# sonar_peripherals.net
KiCad netlist of a schematic drawn in Altium Designer
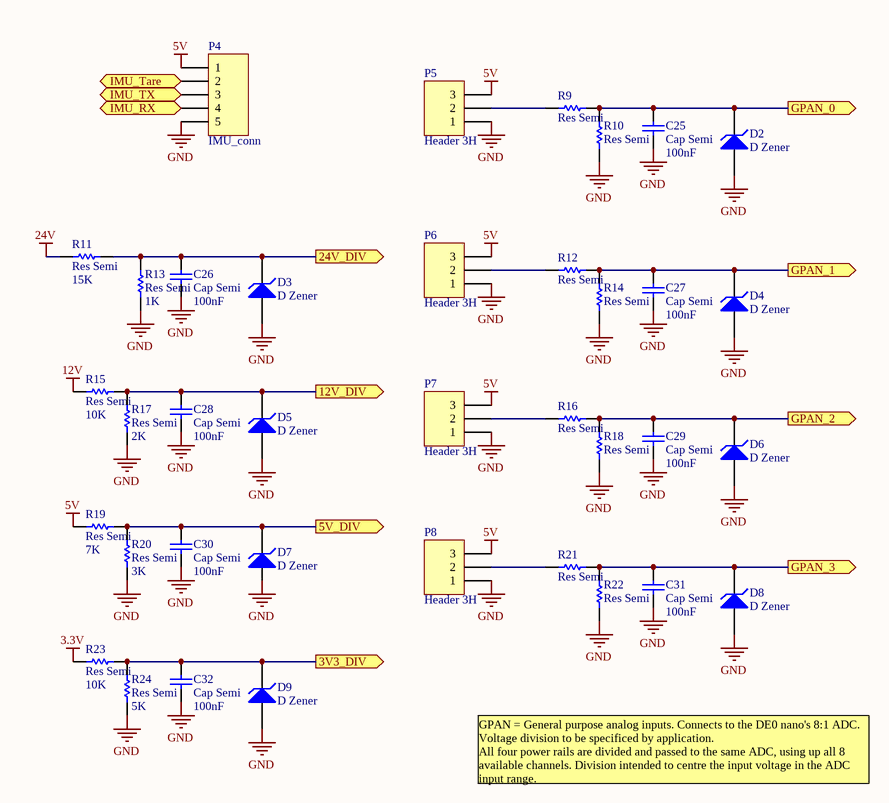
[diagram p0: sonar_peripherals.SchDoc]

(export (version "E")
  (design (tool "Eeschema 10.0.6"))
  (components
    (comp (ref "C25")
      (value "Cap Semi")
      (footprint "C0805")
      (description "Capacitor (Semiconductor SIM Model)")
      (fields (field (name "ALTIUM_VALUE") "100nF") (field (name "PUBLISHER") "Altium Limited"))
      (libsource (lib "Miscellaneous Devices") (part "Cap Semi"))
    )
    (comp (ref "C26")
      (value "Cap Semi")
      (footprint "C0805")
      (description "Capacitor (Semiconductor SIM Model)")
      (fields (field (name "ALTIUM_VALUE") "100nF") (field (name "PUBLISHER") "Altium Limited"))
      (libsource (lib "Miscellaneous Devices") (part "Cap Semi"))
    )
    (comp (ref "C27")
      (value "Cap Semi")
      (footprint "C0805")
      (description "Capacitor (Semiconductor SIM Model)")
      (fields (field (name "ALTIUM_VALUE") "100nF") (field (name "PUBLISHER") "Altium Limited"))
      (libsource (lib "Miscellaneous Devices") (part "Cap Semi"))
    )
    (comp (ref "C28")
      (value "Cap Semi")
      (footprint "C0805")
      (description "Capacitor (Semiconductor SIM Model)")
      (fields (field (name "ALTIUM_VALUE") "100nF") (field (name "PUBLISHER") "Altium Limited"))
      (libsource (lib "Miscellaneous Devices") (part "Cap Semi"))
    )
    (comp (ref "C29")
      (value "Cap Semi")
      (footprint "C0805")
      (description "Capacitor (Semiconductor SIM Model)")
      (fields (field (name "ALTIUM_VALUE") "100nF") (field (name "PUBLISHER") "Altium Limited"))
      (libsource (lib "Miscellaneous Devices") (part "Cap Semi"))
    )
    (comp (ref "C30")
      (value "Cap Semi")
      (footprint "C0805")
      (description "Capacitor (Semiconductor SIM Model)")
      (fields (field (name "ALTIUM_VALUE") "100nF") (field (name "PUBLISHER") "Altium Limited"))
      (libsource (lib "Miscellaneous Devices") (part "Cap Semi"))
    )
    (comp (ref "C31")
      (value "Cap Semi")
      (footprint "C0805")
      (description "Capacitor (Semiconductor SIM Model)")
      (fields (field (name "ALTIUM_VALUE") "100nF") (field (name "PUBLISHER") "Altium Limited"))
      (libsource (lib "Miscellaneous Devices") (part "Cap Semi"))
    )
    (comp (ref "C32")
      (value "Cap Semi")
      (footprint "C0805")
      (description "Capacitor (Semiconductor SIM Model)")
      (fields (field (name "ALTIUM_VALUE") "100nF") (field (name "PUBLISHER") "Altium Limited"))
      (libsource (lib "Miscellaneous Devices") (part "Cap Semi"))
    )
    (comp (ref "D2")
      (value "D Zener")
      (footprint "SOD-323")
      (description "Zener Diode")
      (fields (field (name "PUBLISHER") "Altium Limited"))
      (libsource (lib "Miscellaneous Devices") (part "D Zener"))
    )
    (comp (ref "D3")
      (value "D Zener")
      (footprint "SOD-323")
      (description "Zener Diode")
      (fields (field (name "PUBLISHER") "Altium Limited"))
      (libsource (lib "Miscellaneous Devices") (part "D Zener"))
    )
    (comp (ref "D4")
      (value "D Zener")
      (footprint "SOD-323")
      (description "Zener Diode")
      (fields (field (name "PUBLISHER") "Altium Limited"))
      (libsource (lib "Miscellaneous Devices") (part "D Zener"))
    )
    (comp (ref "D5")
      (value "D Zener")
      (footprint "SOD-323")
      (description "Zener Diode")
      (fields (field (name "PUBLISHER") "Altium Limited"))
      (libsource (lib "Miscellaneous Devices") (part "D Zener"))
    )
    (comp (ref "D6")
      (value "D Zener")
      (footprint "SOD-323")
      (description "Zener Diode")
      (fields (field (name "PUBLISHER") "Altium Limited"))
      (libsource (lib "Miscellaneous Devices") (part "D Zener"))
    )
    (comp (ref "D7")
      (value "D Zener")
      (footprint "SOD-323")
      (description "Zener Diode")
      (fields (field (name "PUBLISHER") "Altium Limited"))
      (libsource (lib "Miscellaneous Devices") (part "D Zener"))
    )
    (comp (ref "D8")
      (value "D Zener")
      (footprint "SOD-323")
      (description "Zener Diode")
      (fields (field (name "PUBLISHER") "Altium Limited"))
      (libsource (lib "Miscellaneous Devices") (part "D Zener"))
    )
    (comp (ref "D9")
      (value "D Zener")
      (footprint "SOD-323")
      (description "Zener Diode")
      (fields (field (name "PUBLISHER") "Altium Limited"))
      (libsource (lib "Miscellaneous Devices") (part "D Zener"))
    )
    (comp (ref "P4")
      (value "IMU_conn")
      (footprint "HDR1X5H")
      (description "Header, 5-Pin, Right Angle")
      (fields (field (name "PUBLISHER") "Altium Limited"))
      (libsource (lib "Miscellaneous Connectors") (part "Header 5H"))
    )
    (comp (ref "P5")
      (value "Header 3H")
      (footprint "HDR1X3H")
      (description "Header, 3-Pin, Right Angle")
      (fields (field (name "PUBLISHER") "Altium Limited"))
      (libsource (lib "Miscellaneous Connectors") (part "Header 3H"))
    )
    (comp (ref "P6")
      (value "Header 3H")
      (footprint "HDR1X3H")
      (description "Header, 3-Pin, Right Angle")
      (fields (field (name "PUBLISHER") "Altium Limited"))
      (libsource (lib "Miscellaneous Connectors") (part "Header 3H"))
    )
    (comp (ref "P7")
      (value "Header 3H")
      (footprint "HDR1X3H")
      (description "Header, 3-Pin, Right Angle")
      (fields (field (name "PUBLISHER") "Altium Limited"))
      (libsource (lib "Miscellaneous Connectors") (part "Header 3H"))
    )
    (comp (ref "P8")
      (value "Header 3H")
      (footprint "HDR1X3H")
      (description "Header, 3-Pin, Right Angle")
      (fields (field (name "PUBLISHER") "Altium Limited"))
      (libsource (lib "Miscellaneous Connectors") (part "Header 3H"))
    )
    (comp (ref "R9")
      (value "Res Semi")
      (footprint "RESC2012L")
      (description "Semiconductor Resistor")
      (fields (field (name "PUBLISHER") "Altium Limited"))
      (libsource (lib "Miscellaneous Devices") (part "Res Semi"))
    )
    (comp (ref "R10")
      (value "Res Semi")
      (footprint "RESC2012L")
      (description "Semiconductor Resistor")
      (fields (field (name "PUBLISHER") "Altium Limited"))
      (libsource (lib "Miscellaneous Devices") (part "Res Semi"))
    )
    (comp (ref "R11")
      (value "Res Semi")
      (footprint "RESC2012L")
      (description "Semiconductor Resistor")
      (fields (field (name "ALTIUM_VALUE") "15K") (field (name "PUBLISHER") "Altium Limited"))
      (libsource (lib "Miscellaneous Devices") (part "Res Semi"))
    )
    (comp (ref "R12")
      (value "Res Semi")
      (footprint "RESC2012L")
      (description "Semiconductor Resistor")
      (fields (field (name "PUBLISHER") "Altium Limited"))
      (libsource (lib "Miscellaneous Devices") (part "Res Semi"))
    )
    (comp (ref "R13")
      (value "Res Semi")
      (footprint "RESC2012L")
      (description "Semiconductor Resistor")
      (fields (field (name "ALTIUM_VALUE") "1K") (field (name "PUBLISHER") "Altium Limited"))
      (libsource (lib "Miscellaneous Devices") (part "Res Semi"))
    )
    (comp (ref "R14")
      (value "Res Semi")
      (footprint "RESC2012L")
      (description "Semiconductor Resistor")
      (fields (field (name "PUBLISHER") "Altium Limited"))
      (libsource (lib "Miscellaneous Devices") (part "Res Semi"))
    )
    (comp (ref "R15")
      (value "Res Semi")
      (footprint "RESC2012L")
      (description "Semiconductor Resistor")
      (fields (field (name "ALTIUM_VALUE") "10K") (field (name "PUBLISHER") "Altium Limited"))
      (libsource (lib "Miscellaneous Devices") (part "Res Semi"))
    )
    (comp (ref "R16")
      (value "Res Semi")
      (footprint "RESC2012L")
      (description "Semiconductor Resistor")
      (fields (field (name "PUBLISHER") "Altium Limited"))
      (libsource (lib "Miscellaneous Devices") (part "Res Semi"))
    )
    (comp (ref "R17")
      (value "Res Semi")
      (footprint "RESC2012L")
      (description "Semiconductor Resistor")
      (fields (field (name "ALTIUM_VALUE") "2K") (field (name "PUBLISHER") "Altium Limited"))
      (libsource (lib "Miscellaneous Devices") (part "Res Semi"))
    )
    (comp (ref "R18")
      (value "Res Semi")
      (footprint "RESC2012L")
      (description "Semiconductor Resistor")
      (fields (field (name "PUBLISHER") "Altium Limited"))
      (libsource (lib "Miscellaneous Devices") (part "Res Semi"))
    )
    (comp (ref "R19")
      (value "Res Semi")
      (footprint "RESC2012L")
      (description "Semiconductor Resistor")
      (fields (field (name "ALTIUM_VALUE") "7K") (field (name "PUBLISHER") "Altium Limited"))
      (libsource (lib "Miscellaneous Devices") (part "Res Semi"))
    )
    (comp (ref "R20")
      (value "Res Semi")
      (footprint "RESC2012L")
      (description "Semiconductor Resistor")
      (fields (field (name "ALTIUM_VALUE") "3K") (field (name "PUBLISHER") "Altium Limited"))
      (libsource (lib "Miscellaneous Devices") (part "Res Semi"))
    )
    (comp (ref "R21")
      (value "Res Semi")
      (footprint "RESC2012L")
      (description "Semiconductor Resistor")
      (fields (field (name "PUBLISHER") "Altium Limited"))
      (libsource (lib "Miscellaneous Devices") (part "Res Semi"))
    )
    (comp (ref "R22")
      (value "Res Semi")
      (footprint "RESC2012L")
      (description "Semiconductor Resistor")
      (fields (field (name "PUBLISHER") "Altium Limited"))
      (libsource (lib "Miscellaneous Devices") (part "Res Semi"))
    )
    (comp (ref "R23")
      (value "Res Semi")
      (footprint "RESC2012L")
      (description "Semiconductor Resistor")
      (fields (field (name "ALTIUM_VALUE") "10K") (field (name "PUBLISHER") "Altium Limited"))
      (libsource (lib "Miscellaneous Devices") (part "Res Semi"))
    )
    (comp (ref "R24")
      (value "Res Semi")
      (footprint "RESC2012L")
      (description "Semiconductor Resistor")
      (fields (field (name "ALTIUM_VALUE") "5K") (field (name "PUBLISHER") "Altium Limited"))
      (libsource (lib "Miscellaneous Devices") (part "Res Semi"))
    )
  )
  (nets
    (net (code "1") (name "/3V3_DIV") (class "Default")
      (node (ref "C32") (pin "2") (pinfunction "2_2") (pintype "passive"))
      (node (ref "D9") (pin "2") (pinfunction "K_2") (pintype "passive"))
      (node (ref "R23") (pin "2") (pinfunction "2_2") (pintype "passive"))
      (node (ref "R24") (pin "2") (pinfunction "2_2") (pintype "passive"))
    )
    (net (code "2") (name "/5V_DIV") (class "Default")
      (node (ref "C30") (pin "2") (pinfunction "2_2") (pintype "passive"))
      (node (ref "D7") (pin "2") (pinfunction "K_2") (pintype "passive"))
      (node (ref "R19") (pin "2") (pinfunction "2_2") (pintype "passive"))
      (node (ref "R20") (pin "2") (pinfunction "2_2") (pintype "passive"))
    )
    (net (code "3") (name "/12V_DIV") (class "Default")
      (node (ref "C28") (pin "2") (pinfunction "2_2") (pintype "passive"))
      (node (ref "D5") (pin "2") (pinfunction "K_2") (pintype "passive"))
      (node (ref "R15") (pin "2") (pinfunction "2_2") (pintype "passive"))
      (node (ref "R17") (pin "2") (pinfunction "2_2") (pintype "passive"))
    )
    (net (code "4") (name "/24V_DIV") (class "Default")
      (node (ref "C26") (pin "2") (pinfunction "2_2") (pintype "passive"))
      (node (ref "D3") (pin "2") (pinfunction "K_2") (pintype "passive"))
      (node (ref "R11") (pin "2") (pinfunction "2_2") (pintype "passive"))
      (node (ref "R13") (pin "2") (pinfunction "2_2") (pintype "passive"))
    )
    (net (code "5") (name "/GPAN_0") (class "Default")
      (node (ref "C25") (pin "2") (pinfunction "2_2") (pintype "passive"))
      (node (ref "D2") (pin "2") (pinfunction "K_2") (pintype "passive"))
      (node (ref "R10") (pin "2") (pinfunction "2_2") (pintype "passive"))
      (node (ref "R9") (pin "2") (pinfunction "2_2") (pintype "passive"))
    )
    (net (code "6") (name "/GPAN_1") (class "Default")
      (node (ref "C27") (pin "2") (pinfunction "2_2") (pintype "passive"))
      (node (ref "D4") (pin "2") (pinfunction "K_2") (pintype "passive"))
      (node (ref "R12") (pin "2") (pinfunction "2_2") (pintype "passive"))
      (node (ref "R14") (pin "2") (pinfunction "2_2") (pintype "passive"))
    )
    (net (code "7") (name "/GPAN_2") (class "Default")
      (node (ref "C29") (pin "2") (pinfunction "2_2") (pintype "passive"))
      (node (ref "D6") (pin "2") (pinfunction "K_2") (pintype "passive"))
      (node (ref "R16") (pin "2") (pinfunction "2_2") (pintype "passive"))
      (node (ref "R18") (pin "2") (pinfunction "2_2") (pintype "passive"))
    )
    (net (code "8") (name "/GPAN_3") (class "Default")
      (node (ref "C31") (pin "2") (pinfunction "2_2") (pintype "passive"))
      (node (ref "D8") (pin "2") (pinfunction "K_2") (pintype "passive"))
      (node (ref "R21") (pin "2") (pinfunction "2_2") (pintype "passive"))
      (node (ref "R22") (pin "2") (pinfunction "2_2") (pintype "passive"))
    )
    (net (code "9") (name "/IMU_RX") (class "Default")
      (node (ref "P4") (pin "4") (pinfunction "4_4") (pintype "passive"))
    )
    (net (code "10") (name "/IMU_TX") (class "Default")
      (node (ref "P4") (pin "3") (pinfunction "3_3") (pintype "passive"))
    )
    (net (code "11") (name "/IMU_Tare") (class "Default")
      (node (ref "P4") (pin "2") (pinfunction "2_2") (pintype "passive"))
    )
    (net (code "12") (name "3.3V") (class "Default")
      (node (ref "R23") (pin "1") (pinfunction "1_1") (pintype "passive"))
    )
    (net (code "13") (name "5V") (class "Default")
      (node (ref "P4") (pin "1") (pinfunction "1_1") (pintype "passive"))
      (node (ref "P5") (pin "3") (pinfunction "3_3") (pintype "passive"))
      (node (ref "P6") (pin "3") (pinfunction "3_3") (pintype "passive"))
      (node (ref "P7") (pin "3") (pinfunction "3_3") (pintype "passive"))
      (node (ref "P8") (pin "3") (pinfunction "3_3") (pintype "passive"))
      (node (ref "R19") (pin "1") (pinfunction "1_1") (pintype "passive"))
    )
    (net (code "14") (name "12V") (class "Default")
      (node (ref "R15") (pin "1") (pinfunction "1_1") (pintype "passive"))
    )
    (net (code "15") (name "24V") (class "Default")
      (node (ref "R11") (pin "1") (pinfunction "1_1") (pintype "passive"))
    )
    (net (code "16") (name "GND") (class "Default")
      (node (ref "C25") (pin "1") (pinfunction "1_1") (pintype "passive"))
      (node (ref "C26") (pin "1") (pinfunction "1_1") (pintype "passive"))
      (node (ref "C27") (pin "1") (pinfunction "1_1") (pintype "passive"))
      (node (ref "C28") (pin "1") (pinfunction "1_1") (pintype "passive"))
      (node (ref "C29") (pin "1") (pinfunction "1_1") (pintype "passive"))
      (node (ref "C30") (pin "1") (pinfunction "1_1") (pintype "passive"))
      (node (ref "C31") (pin "1") (pinfunction "1_1") (pintype "passive"))
      (node (ref "C32") (pin "1") (pinfunction "1_1") (pintype "passive"))
      (node (ref "D2") (pin "1") (pinfunction "A_1") (pintype "passive"))
      (node (ref "D3") (pin "1") (pinfunction "A_1") (pintype "passive"))
      (node (ref "D4") (pin "1") (pinfunction "A_1") (pintype "passive"))
      (node (ref "D5") (pin "1") (pinfunction "A_1") (pintype "passive"))
      (node (ref "D6") (pin "1") (pinfunction "A_1") (pintype "passive"))
      (node (ref "D8") (pin "1") (pinfunction "A_1") (pintype "passive"))
      (node (ref "D9") (pin "1") (pinfunction "A_1") (pintype "passive"))
      (node (ref "P4") (pin "5") (pinfunction "5_5") (pintype "passive"))
      (node (ref "P5") (pin "1") (pinfunction "1_1") (pintype "passive"))
      (node (ref "P6") (pin "1") (pinfunction "1_1") (pintype "passive"))
      (node (ref "P7") (pin "1") (pinfunction "1_1") (pintype "passive"))
      (node (ref "P8") (pin "1") (pinfunction "1_1") (pintype "passive"))
      (node (ref "R10") (pin "1") (pinfunction "1_1") (pintype "passive"))
      (node (ref "R13") (pin "1") (pinfunction "1_1") (pintype "passive"))
      (node (ref "R14") (pin "1") (pinfunction "1_1") (pintype "passive"))
      (node (ref "R17") (pin "1") (pinfunction "1_1") (pintype "passive"))
      (node (ref "R18") (pin "1") (pinfunction "1_1") (pintype "passive"))
      (node (ref "R20") (pin "1") (pinfunction "1_1") (pintype "passive"))
      (node (ref "R22") (pin "1") (pinfunction "1_1") (pintype "passive"))
      (node (ref "R24") (pin "1") (pinfunction "1_1") (pintype "passive"))
    )
    (net (code "17") (name "Net-(P5-Pad2)") (class "Default")
      (node (ref "P5") (pin "2") (pinfunction "2_2") (pintype "passive"))
      (node (ref "R9") (pin "1") (pinfunction "1_1") (pintype "passive"))
    )
    (net (code "18") (name "Net-(P6-Pad2)") (class "Default")
      (node (ref "P6") (pin "2") (pinfunction "2_2") (pintype "passive"))
      (node (ref "R12") (pin "1") (pinfunction "1_1") (pintype "passive"))
    )
    (net (code "19") (name "Net-(P7-Pad2)") (class "Default")
      (node (ref "P7") (pin "2") (pinfunction "2_2") (pintype "passive"))
      (node (ref "R16") (pin "1") (pinfunction "1_1") (pintype "passive"))
    )
    (net (code "20") (name "Net-(P8-Pad2)") (class "Default")
      (node (ref "P8") (pin "2") (pinfunction "2_2") (pintype "passive"))
      (node (ref "R21") (pin "1") (pinfunction "1_1") (pintype "passive"))
    )
    (net (code "21") (name "unconnected-(D7-A-Pad1)") (class "Default")
      (node (ref "D7") (pin "1") (pinfunction "A_1") (pintype "passive"))
    )
  )
)
